# heater.net
KiCad netlist of a schematic drawn in EAGLE
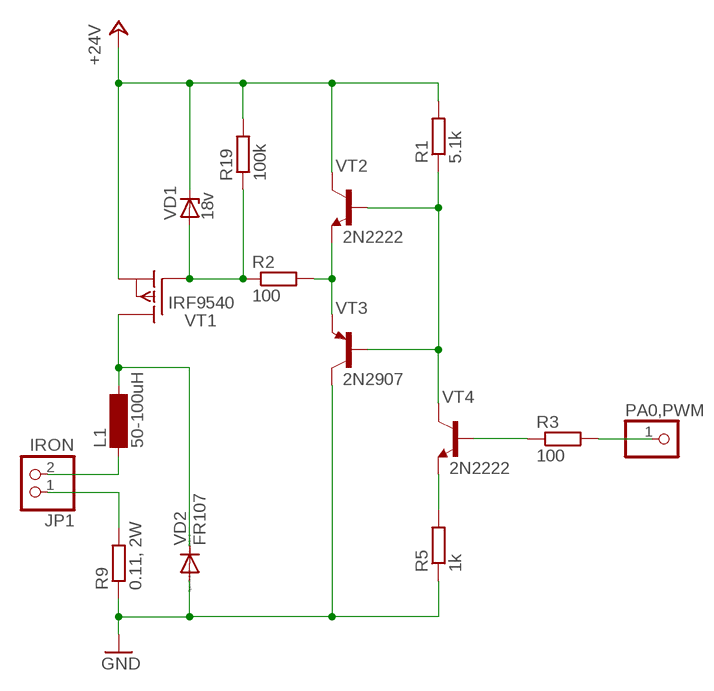
[diagram p0: schematic, sheet 1]

(export (version "E")
  (design (tool "Eeschema 10.0.6"))
  (components
    (comp (ref "JP1")
      (value "IRON")
      (footprint "eagle-import:1X02")
      (libsource (lib "eagle-import") (part "PINHD-1X2"))
    )
    (comp (ref "L1")
      (value "50-100uH")
      (footprint "eagle-import:SD8")
      (libsource (lib "eagle-import") (part "SD8"))
    )
    (comp (ref "PA0,PWM")
      (value "PINHD-1X1")
      (footprint "eagle-import:1X01")
      (libsource (lib "eagle-import") (part "PINHD-1X1"))
    )
    (comp (ref "R1")
      (value "5.1k")
      (footprint "eagle-import:0207_10")
      (libsource (lib "eagle-import") (part "R-EU_0207/10"))
    )
    (comp (ref "R2")
      (value "100")
      (footprint "eagle-import:0207_10")
      (libsource (lib "eagle-import") (part "R-EU_0207/10"))
    )
    (comp (ref "R3")
      (value "100")
      (footprint "eagle-import:0207_10")
      (libsource (lib "eagle-import") (part "R-EU_0207/10"))
    )
    (comp (ref "R5")
      (value "1k")
      (footprint "eagle-import:0207_10")
      (libsource (lib "eagle-import") (part "R-EU_0207/10"))
    )
    (comp (ref "R9")
      (value "0.11, 2W")
      (footprint "eagle-import:0207_10")
      (libsource (lib "eagle-import") (part "R-EU_0207/10"))
    )
    (comp (ref "R19")
      (value "100k")
      (footprint "eagle-import:0207_10")
      (libsource (lib "eagle-import") (part "R-EU_0207/10"))
    )
    (comp (ref "VD1")
      (value "18v")
      (footprint "eagle-import:C1702-15")
      (libsource (lib "eagle-import") (part "ZENER-DIODEC1702-15"))
    )
    (comp (ref "VD2")
      (value "FR107")
      (footprint "eagle-import:DO41-10")
      (libsource (lib "eagle-import") (part "1N4004"))
    )
    (comp (ref "VT1")
      (value "IRF9540")
      (footprint "eagle-import:TO220")
      (libsource (lib "eagle-import") (part "IRF9530"))
    )
    (comp (ref "VT2")
      (value "2N2222")
      (footprint "eagle-import:TO18")
      (libsource (lib "eagle-import") (part "2N2222"))
    )
    (comp (ref "VT3")
      (value "2N2907")
      (footprint "eagle-import:TO18")
      (libsource (lib "eagle-import") (part "-PNP-TO18-EBC2N2907"))
    )
    (comp (ref "VT4")
      (value "2N2222")
      (footprint "eagle-import:TO18")
      (libsource (lib "eagle-import") (part "2N2222"))
    )
  )
  (nets
    (net (code "1") (name "+24V") (class "Default")
      (node (ref "R1") (pin "2") (pinfunction "2_2") (pintype "passive"))
      (node (ref "R19") (pin "2") (pinfunction "2_2") (pintype "passive"))
      (node (ref "VD1") (pin "C") (pinfunction "C_C") (pintype "passive"))
      (node (ref "VT1") (pin "3") (pinfunction "S_3") (pintype "passive"))
      (node (ref "VT2") (pin "3") (pinfunction "C_3") (pintype "passive"))
    )
    (net (code "2") (name "GND") (class "Default")
      (node (ref "R5") (pin "1") (pinfunction "1_1") (pintype "passive"))
      (node (ref "R9") (pin "1") (pinfunction "1_1") (pintype "passive"))
      (node (ref "VD2") (pin "A") (pinfunction "A_A") (pintype "passive"))
      (node (ref "VT3") (pin "3") (pinfunction "C_3") (pintype "passive"))
    )
    (net (code "3") (name "Net-(JP1-Pad1)") (class "Default")
      (node (ref "JP1") (pin "1") (pinfunction "1_1") (pintype "passive"))
      (node (ref "R9") (pin "2") (pinfunction "2_2") (pintype "passive"))
    )
    (net (code "4") (name "Net-(JP1-Pad2)") (class "Default")
      (node (ref "JP1") (pin "2") (pinfunction "2_2") (pintype "passive"))
      (node (ref "L1") (pin "1") (pinfunction "1_1") (pintype "passive"))
    )
    (net (code "5") (name "Net-(PA0,PWM-Pad1)") (class "Default")
      (node (ref "PA0,PWM") (pin "1") (pinfunction "1_1") (pintype "passive"))
      (node (ref "R3") (pin "2") (pinfunction "2_2") (pintype "passive"))
    )
    (net (code "6") (name "Net-(VT1-D)") (class "Default")
      (node (ref "L1") (pin "2") (pinfunction "2_2") (pintype "passive"))
      (node (ref "VD2") (pin "C") (pinfunction "C_C") (pintype "passive"))
      (node (ref "VT1") (pin "2") (pinfunction "D_2") (pintype "passive"))
    )
    (net (code "7") (name "Net-(VT1-G)") (class "Default")
      (node (ref "R19") (pin "1") (pinfunction "1_1") (pintype "passive"))
      (node (ref "R2") (pin "1") (pinfunction "1_1") (pintype "passive"))
      (node (ref "VD1") (pin "A") (pinfunction "A_A") (pintype "passive"))
      (node (ref "VT1") (pin "1") (pinfunction "G_1") (pintype "passive"))
    )
    (net (code "8") (name "Net-(VT2-B)") (class "Default")
      (node (ref "R1") (pin "1") (pinfunction "1_1") (pintype "passive"))
      (node (ref "VT2") (pin "2") (pinfunction "B_2") (pintype "passive"))
      (node (ref "VT3") (pin "2") (pinfunction "B_2") (pintype "passive"))
      (node (ref "VT4") (pin "3") (pinfunction "C_3") (pintype "passive"))
    )
    (net (code "9") (name "Net-(VT2-E)") (class "Default")
      (node (ref "R2") (pin "2") (pinfunction "2_2") (pintype "passive"))
      (node (ref "VT2") (pin "1") (pinfunction "E_1") (pintype "passive"))
      (node (ref "VT3") (pin "1") (pinfunction "E_1") (pintype "passive"))
    )
    (net (code "10") (name "Net-(VT4-B)") (class "Default")
      (node (ref "R3") (pin "1") (pinfunction "1_1") (pintype "passive"))
      (node (ref "VT4") (pin "2") (pinfunction "B_2") (pintype "passive"))
    )
    (net (code "11") (name "Net-(VT4-E)") (class "Default")
      (node (ref "R5") (pin "2") (pinfunction "2_2") (pintype "passive"))
      (node (ref "VT4") (pin "1") (pinfunction "E_1") (pintype "passive"))
    )
  )
)
